# untitled.net
KiCad netlist of a schematic drawn in EAGLE
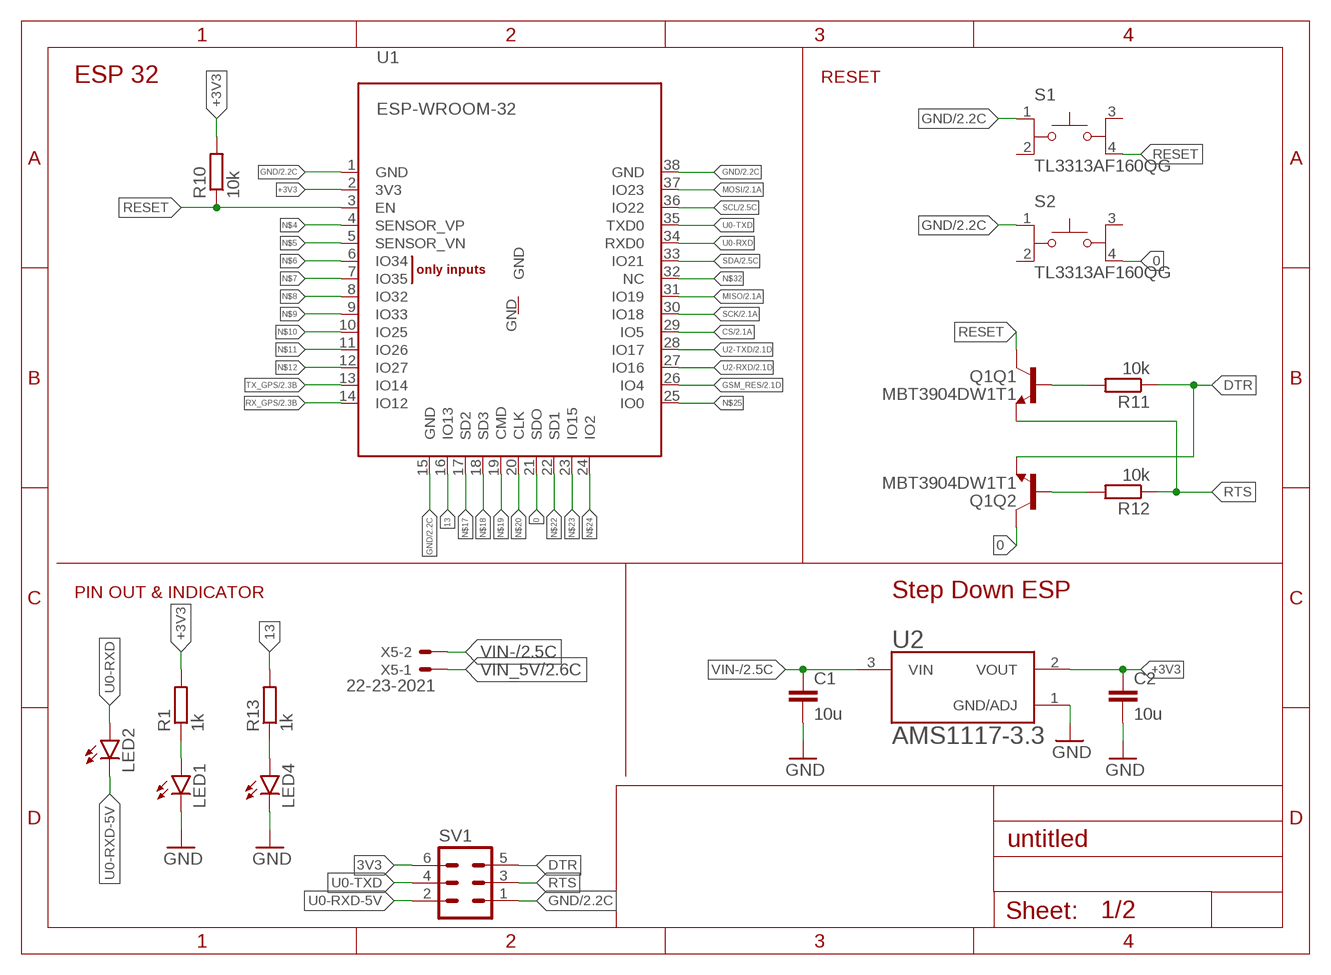
[diagram p0: schematic, sheet 1]
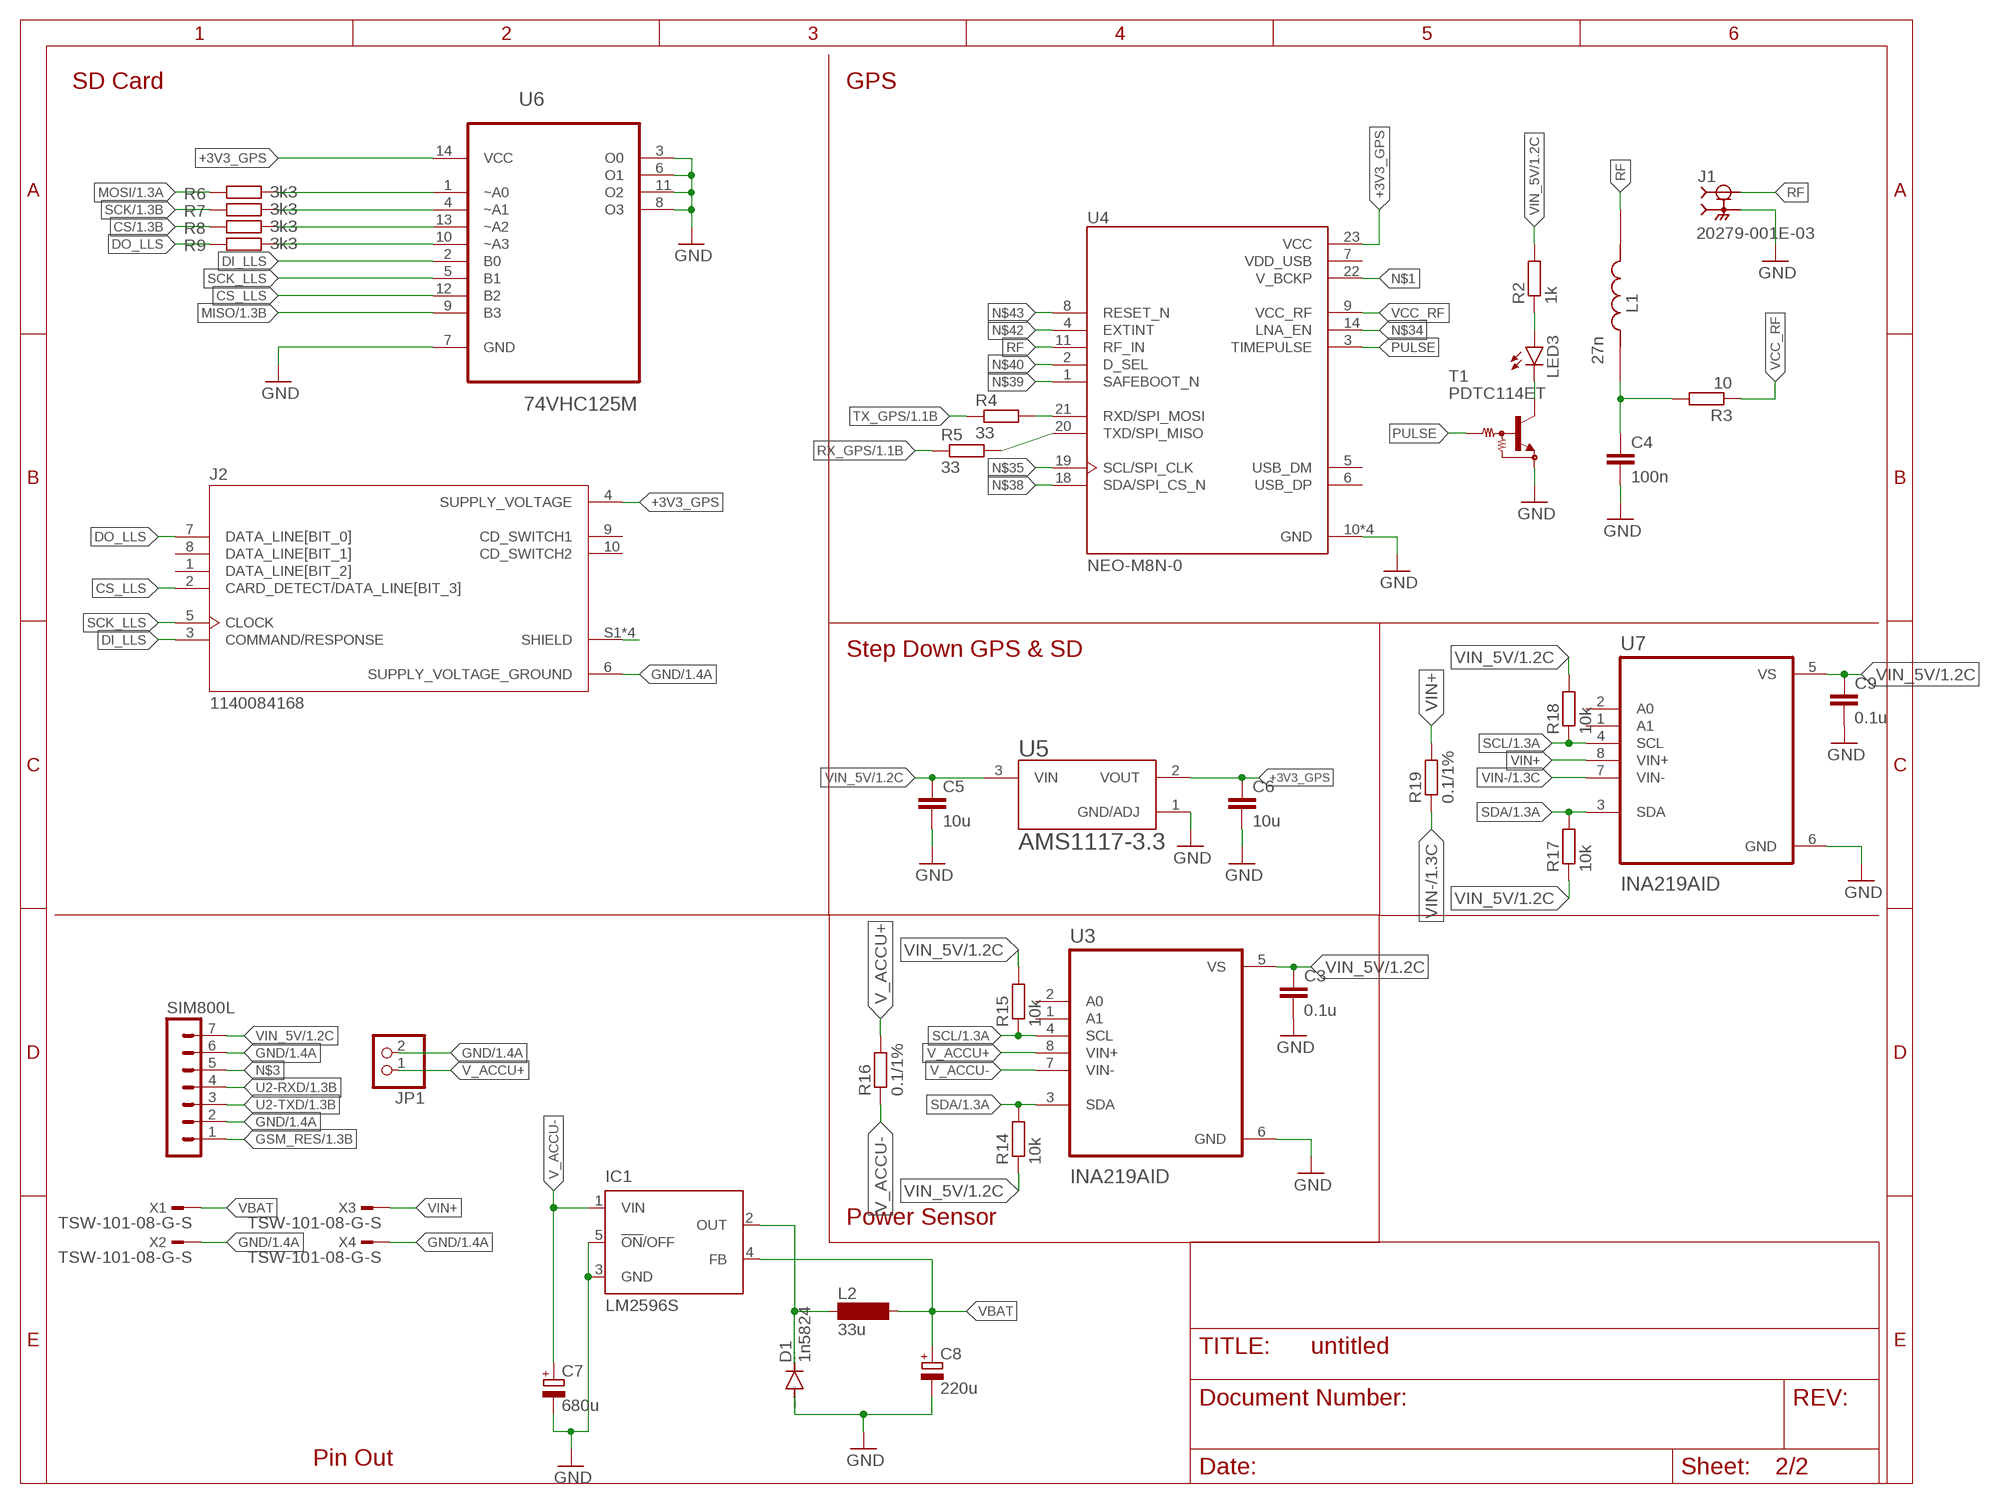
[diagram p1: schematic, sheet 2]

(export (version "E")
  (design (tool "Eeschema 10.0.6"))
  (components
    (comp (ref "C1")
      (value "10u")
      (footprint "eagle-import:C0805K")
      (libsource (lib "eagle-import") (part "C-EUC0805K"))
    )
    (comp (ref "C2")
      (value "10u")
      (footprint "eagle-import:C0805K")
      (libsource (lib "eagle-import") (part "C-EUC0805K"))
    )
    (comp (ref "LED1")
      (value "LEDCHIPLED_0805")
      (footprint "eagle-import:CHIPLED_0805")
      (libsource (lib "eagle-import") (part "LEDCHIPLED_0805"))
    )
    (comp (ref "LED2")
      (value "LEDCHIPLED_0805")
      (footprint "eagle-import:CHIPLED_0805")
      (libsource (lib "eagle-import") (part "LEDCHIPLED_0805"))
    )
    (comp (ref "LED4")
      (value "LEDCHIPLED_0805")
      (footprint "eagle-import:CHIPLED_0805")
      (libsource (lib "eagle-import") (part "LEDCHIPLED_0805"))
    )
    (comp (ref "Q1")
      (value "MBT3904DW1T1")
      (footprint "eagle-import:SC70-6")
      (fields (field (name "MF") "ON Semiconductor"))
      (libsource (lib "eagle-import") (part "MBT3904DW1T1"))
    )
    (comp (ref "R1")
      (value "1k")
      (footprint "eagle-import:M0805")
      (libsource (lib "eagle-import") (part "R-EU_M0805"))
    )
    (comp (ref "R10")
      (value "10k")
      (footprint "eagle-import:M0805")
      (libsource (lib "eagle-import") (part "R-EU_M0805"))
    )
    (comp (ref "R11")
      (value "10k")
      (footprint "eagle-import:M0805")
      (libsource (lib "eagle-import") (part "R-EU_M0805"))
    )
    (comp (ref "R12")
      (value "10k")
      (footprint "eagle-import:M0805")
      (libsource (lib "eagle-import") (part "R-EU_M0805"))
    )
    (comp (ref "R13")
      (value "1k")
      (footprint "eagle-import:M0805")
      (libsource (lib "eagle-import") (part "R-EU_M0805"))
    )
    (comp (ref "S1")
      (value "TL3313AF160QG")
      (footprint "eagle-import:SW_TL3313AF160QG")
      (fields (field (name "MF") "E-Switch"))
      (libsource (lib "eagle-import") (part "TL3313AF160QG"))
    )
    (comp (ref "S2")
      (value "TL3313AF160QG")
      (footprint "eagle-import:SW_TL3313AF160QG")
      (fields (field (name "MF") "E-Switch"))
      (libsource (lib "eagle-import") (part "TL3313AF160QG"))
    )
    (comp (ref "SV1")
      (value "MA03-2")
      (footprint "eagle-import:MA03-2")
      (libsource (lib "eagle-import") (part "MA03-2"))
    )
    (comp (ref "U1")
      (value "ESP-WROOM-32")
      (footprint "eagle-import:ESP-WROOM-32")
      (libsource (lib "eagle-import") (part "ESP-WROOM-32"))
    )
    (comp (ref "U2")
      (value "AMS1117-3.3")
      (footprint "eagle-import:SOT229P700X180-4N")
      (fields (field (name "MF") "Advanced Monolithic Systems"))
      (libsource (lib "eagle-import") (part "AMS1117-3.3"))
    )
    (comp (ref "X5")
      (value "22-23-2021")
      (footprint "eagle-import:22-23-2021")
      (fields (field (name "MF") "MOLEX"))
      (libsource (lib "eagle-import") (part "22-23-2021"))
    )
    (comp (ref "C3")
      (value "0.1u")
      (footprint "eagle-import:C0805")
      (libsource (lib "eagle-import") (part "C-EUC0805"))
    )
    (comp (ref "C4")
      (value "100n")
      (footprint "eagle-import:C0603K")
      (libsource (lib "eagle-import") (part "C-EUC0603K"))
    )
    (comp (ref "C5")
      (value "10u")
      (footprint "eagle-import:C0805K")
      (libsource (lib "eagle-import") (part "C-EUC0805K"))
    )
    (comp (ref "C6")
      (value "10u")
      (footprint "eagle-import:C0805K")
      (libsource (lib "eagle-import") (part "C-EUC0805K"))
    )
    (comp (ref "C7")
      (value "680u")
      (footprint "eagle-import:153CLV-0605")
      (libsource (lib "eagle-import") (part "CPOL-EU153CLV-0605"))
    )
    (comp (ref "C8")
      (value "220u")
      (footprint "eagle-import:153CLV-0605")
      (libsource (lib "eagle-import") (part "CPOL-EU153CLV-0605"))
    )
    (comp (ref "C9")
      (value "0.1u")
      (footprint "eagle-import:C0805")
      (libsource (lib "eagle-import") (part "C-EUC0805"))
    )
    (comp (ref "D1")
      (value "1n5824")
      (footprint "eagle-import:DO-214AC")
      (libsource (lib "eagle-import") (part "DIODE-DO-214AC"))
    )
    (comp (ref "IC1")
      (value "LM2596S")
      (footprint "eagle-import:TO263-5")
      (fields (field (name "MF") "NATIONAL SEMICONDUCTOR") (field (name "MPN") "LM2596S-ADJ/NOPB"))
      (libsource (lib "eagle-import") (part "LM2596S"))
    )
    (comp (ref "J1")
      (value "20279-001E-03")
      (footprint "eagle-import:IPEX_20279-001E-03")
      (fields (field (name "MF") "I-PEX"))
      (libsource (lib "eagle-import") (part "20279-001E-03"))
    )
    (comp (ref "J2")
      (value "1140084168")
      (footprint "eagle-import:AMPHENOL_1140084168")
      (fields (field (name "MF") "Amphenol ICC (Commercial Products)") (field (name "MP") "114-00841-68"))
      (libsource (lib "eagle-import") (part "1140084168"))
    )
    (comp (ref "JP1")
      (value "PINHD-1X2")
      (footprint "eagle-import:1X02")
      (libsource (lib "eagle-import") (part "PINHD-1X2"))
    )
    (comp (ref "L1")
      (value "27n")
      (footprint "eagle-import:INDC2012X105N")
      (fields (field (name "MF") "TDK") (field (name "MP") "MLZ2012A1R0WT000"))
      (libsource (lib "eagle-import") (part "MLZ2012A1R0WT000"))
    )
    (comp (ref "L2")
      (value "33u")
      (footprint "eagle-import:MS85")
      (libsource (lib "eagle-import") (part "MS85"))
    )
    (comp (ref "LED3")
      (value "LEDCHIPLED_0805")
      (footprint "eagle-import:CHIPLED_0805")
      (libsource (lib "eagle-import") (part "LEDCHIPLED_0805"))
    )
    (comp (ref "R2")
      (value "1k")
      (footprint "eagle-import:M0805")
      (libsource (lib "eagle-import") (part "R-EU_M0805"))
    )
    (comp (ref "R3")
      (value "10")
      (footprint "eagle-import:M1206")
      (libsource (lib "eagle-import") (part "R-EU_M1206"))
    )
    (comp (ref "R4")
      (value "33")
      (footprint "eagle-import:R1206")
      (libsource (lib "eagle-import") (part "R-EU_R1206"))
    )
    (comp (ref "R5")
      (value "33")
      (footprint "eagle-import:R1206")
      (libsource (lib "eagle-import") (part "R-EU_R1206"))
    )
    (comp (ref "R6")
      (value "3k3")
      (footprint "eagle-import:M0805")
      (libsource (lib "eagle-import") (part "R-EU_M0805"))
    )
    (comp (ref "R7")
      (value "3k3")
      (footprint "eagle-import:M0805")
      (libsource (lib "eagle-import") (part "R-EU_M0805"))
    )
    (comp (ref "R8")
      (value "3k3")
      (footprint "eagle-import:M0805")
      (libsource (lib "eagle-import") (part "R-EU_M0805"))
    )
    (comp (ref "R9")
      (value "3k3")
      (footprint "eagle-import:M0805")
      (libsource (lib "eagle-import") (part "R-EU_M0805"))
    )
    (comp (ref "R14")
      (value "10k")
      (footprint "eagle-import:M0805")
      (libsource (lib "eagle-import") (part "R-EU_M0805"))
    )
    (comp (ref "R15")
      (value "10k")
      (footprint "eagle-import:M0805")
      (libsource (lib "eagle-import") (part "R-EU_M0805"))
    )
    (comp (ref "R16")
      (value "0.1/1%")
      (footprint "eagle-import:M1206")
      (libsource (lib "eagle-import") (part "R-EU_M1206"))
    )
    (comp (ref "R17")
      (value "10k")
      (footprint "eagle-import:M0805")
      (libsource (lib "eagle-import") (part "R-EU_M0805"))
    )
    (comp (ref "R18")
      (value "10k")
      (footprint "eagle-import:M0805")
      (libsource (lib "eagle-import") (part "R-EU_M0805"))
    )
    (comp (ref "R19")
      (value "0.1/1%")
      (footprint "eagle-import:M1206")
      (libsource (lib "eagle-import") (part "R-EU_M1206"))
    )
    (comp (ref "SIM800L")
      (value "MA07-1")
      (footprint "eagle-import:MA07-1")
      (libsource (lib "eagle-import") (part "MA07-1"))
    )
    (comp (ref "T1")
      (value "PDTC114ET")
      (footprint "eagle-import:SC59-BEC")
      (libsource (lib "eagle-import") (part "-NPN_DRIVER-SC59-BECMUN2211T1"))
    )
    (comp (ref "U3")
      (value "INA219AID")
      (footprint "eagle-import:SOIC127P599X175-8N")
      (fields (field (name "MF") "Texas Instruments"))
      (libsource (lib "eagle-import") (part "INA219AID"))
    )
    (comp (ref "U4")
      (value "NEO-M8N-0")
      (footprint "eagle-import:XCVR_NEO-M8N-0")
      (fields (field (name "MF") "U-Blox America"))
      (libsource (lib "eagle-import") (part "NEO-M8N-0"))
    )
    (comp (ref "U5")
      (value "AMS1117-3.3")
      (footprint "eagle-import:SOT229P700X180-4N")
      (fields (field (name "MF") "Advanced Monolithic Systems"))
      (libsource (lib "eagle-import") (part "AMS1117-3.3"))
    )
    (comp (ref "U6")
      (value "74VHC125M")
      (footprint "eagle-import:SOIC127P600X175-14N")
      (fields (field (name "MF") "ON Semiconductor"))
      (libsource (lib "eagle-import") (part "74VHC125M"))
    )
    (comp (ref "U7")
      (value "INA219AID")
      (footprint "eagle-import:SOIC127P599X175-8N")
      (fields (field (name "MF") "Texas Instruments"))
      (libsource (lib "eagle-import") (part "INA219AID"))
    )
    (comp (ref "X1")
      (value "TSW-101-08-G-S")
      (footprint "eagle-import:TSW-101-XX-G-S")
      (fields (field (name "MF") "Samtec Inc.") (field (name "MPN") "TSW-101-07-G-S"))
      (libsource (lib "eagle-import") (part "TSW-101--G-S08"))
    )
    (comp (ref "X2")
      (value "TSW-101-08-G-S")
      (footprint "eagle-import:TSW-101-XX-G-S")
      (fields (field (name "MF") "Samtec Inc.") (field (name "MPN") "TSW-101-07-G-S"))
      (libsource (lib "eagle-import") (part "TSW-101--G-S08"))
    )
    (comp (ref "X3")
      (value "TSW-101-08-G-S")
      (footprint "eagle-import:TSW-101-XX-G-S")
      (fields (field (name "MF") "Samtec Inc.") (field (name "MPN") "TSW-101-07-G-S"))
      (libsource (lib "eagle-import") (part "TSW-101--G-S08"))
    )
    (comp (ref "X4")
      (value "TSW-101-08-G-S")
      (footprint "eagle-import:TSW-101-XX-G-S")
      (fields (field (name "MF") "Samtec Inc.") (field (name "MPN") "TSW-101-07-G-S"))
      (libsource (lib "eagle-import") (part "TSW-101--G-S08"))
    )
  )
  (nets
    (net (code "1") (name "+3V3") (class "Default")
      (node (ref "C2") (pin "1") (pinfunction "1_1") (pintype "passive"))
      (node (ref "R1") (pin "2") (pinfunction "2_2") (pintype "passive"))
      (node (ref "R10") (pin "2") (pinfunction "2_2") (pintype "passive"))
      (node (ref "U1") (pin "2") (pinfunction "3V3_2") (pintype "bidirectional"))
      (node (ref "U2") (pin "2") (pinfunction "VOUT_2") (pintype "output"))
    )
    (net (code "2") (name "+3V3_GPS") (class "Default")
      (node (ref "C6") (pin "1") (pinfunction "1_1") (pintype "passive"))
      (node (ref "J2") (pin "4") (pinfunction "SUPPLY_VOLTAGE_4") (pintype "power_in"))
      (node (ref "U4") (pin "23") (pinfunction "VCC_23") (pintype "power_in"))
      (node (ref "U5") (pin "2") (pinfunction "VOUT_2") (pintype "output"))
      (node (ref "U6") (pin "14") (pinfunction "VCC_14") (pintype "power_in"))
    )
    (net (code "3") (name "0") (class "Default")
      (node (ref "Q1") (pin "6") (pinfunction "C_6") (pintype "passive"))
      (node (ref "S2") (pin "4") (pinfunction "4_4") (pintype "passive"))
      (node (ref "U1") (pin "21") (pinfunction "SDO_21") (pintype "bidirectional"))
    )
    (net (code "4") (name "3V3") (class "Default")
      (node (ref "SV1") (pin "6") (pinfunction "6_6") (pintype "passive"))
    )
    (net (code "5") (name "13") (class "Default")
      (node (ref "R13") (pin "2") (pinfunction "2_2") (pintype "passive"))
      (node (ref "U1") (pin "16") (pinfunction "IO13_16") (pintype "bidirectional"))
    )
    (net (code "6") (name "CS") (class "Default")
      (node (ref "R8") (pin "1") (pinfunction "1_1") (pintype "passive"))
      (node (ref "U1") (pin "29") (pinfunction "IO5_29") (pintype "bidirectional"))
    )
    (net (code "7") (name "CS_LLS") (class "Default")
      (node (ref "J2") (pin "2") (pinfunction "CARD_DETECT/DATA_LINE[BIT_3]_2") (pintype "bidirectional"))
      (node (ref "U6") (pin "12") (pinfunction "B2_12") (pintype "input"))
    )
    (net (code "8") (name "DI_LLS") (class "Default")
      (node (ref "J2") (pin "3") (pinfunction "COMMAND/RESPONSE_3") (pintype "bidirectional"))
      (node (ref "U6") (pin "2") (pinfunction "B0_2") (pintype "input"))
    )
    (net (code "9") (name "DO_LLS") (class "Default")
      (node (ref "J2") (pin "7") (pinfunction "DATA_LINE[BIT_0]_7") (pintype "bidirectional"))
      (node (ref "R9") (pin "1") (pinfunction "1_1") (pintype "passive"))
    )
    (net (code "10") (name "DTR") (class "Default")
      (node (ref "Q1") (pin "1") (pinfunction "E_1") (pintype "passive"))
      (node (ref "R11") (pin "1") (pinfunction "1_1") (pintype "passive"))
      (node (ref "SV1") (pin "5") (pinfunction "5_5") (pintype "passive"))
    )
    (net (code "11") (name "GND") (class "Default")
      (node (ref "C1") (pin "2") (pinfunction "2_2") (pintype "passive"))
      (node (ref "C2") (pin "2") (pinfunction "2_2") (pintype "passive"))
      (node (ref "C3") (pin "2") (pinfunction "2_2") (pintype "passive"))
      (node (ref "C4") (pin "2") (pinfunction "2_2") (pintype "passive"))
      (node (ref "C5") (pin "2") (pinfunction "2_2") (pintype "passive"))
      (node (ref "C6") (pin "2") (pinfunction "2_2") (pintype "passive"))
      (node (ref "C7") (pin "-") (pinfunction "-_-") (pintype "passive"))
      (node (ref "C8") (pin "-") (pinfunction "-_-") (pintype "passive"))
      (node (ref "C9") (pin "2") (pinfunction "2_2") (pintype "passive"))
      (node (ref "D1") (pin "A") (pinfunction "A_A") (pintype "passive"))
      (node (ref "IC1") (pin "3") (pinfunction "GND_3") (pintype "power_in"))
      (node (ref "IC1") (pin "5") (pinfunction "~{ON}/OFF_5") (pintype "input"))
      (node (ref "J1") (pin "2") (pinfunction "GND_2") (pintype "passive"))
      (node (ref "J1") (pin "3") (pinfunction "GND_3") (pintype "passive"))
      (node (ref "J2") (pin "6") (pinfunction "SUPPLY_VOLTAGE_GROUND_6") (pintype "power_in"))
      (node (ref "JP1") (pin "2") (pinfunction "2_2") (pintype "passive"))
      (node (ref "LED1") (pin "C") (pinfunction "C_C") (pintype "passive"))
      (node (ref "LED4") (pin "C") (pinfunction "C_C") (pintype "passive"))
      (node (ref "S1") (pin "1") (pinfunction "1_1") (pintype "passive"))
      (node (ref "S2") (pin "1") (pinfunction "1_1") (pintype "passive"))
      (node (ref "SIM800L") (pin "2") (pinfunction "2_2") (pintype "passive"))
      (node (ref "SIM800L") (pin "6") (pinfunction "6_6") (pintype "passive"))
      (node (ref "SV1") (pin "1") (pinfunction "1_1") (pintype "passive"))
      (node (ref "T1") (pin "E") (pinfunction "E_E") (pintype "passive"))
      (node (ref "U1") (pin "1") (pinfunction "GND_1") (pintype "bidirectional"))
      (node (ref "U1") (pin "15") (pinfunction "GND_15") (pintype "bidirectional"))
      (node (ref "U1") (pin "38") (pinfunction "GND_38") (pintype "bidirectional"))
      (node (ref "U2") (pin "1") (pinfunction "GND/ADJ_1") (pintype "power_in"))
      (node (ref "U3") (pin "6") (pinfunction "GND_6") (pintype "power_in"))
      (node (ref "U4") (pin "10") (pinfunction "GND_10") (pintype "power_in"))
      (node (ref "U4") (pin "12") (pinfunction "GND_12") (pintype "power_in"))
      (node (ref "U4") (pin "13") (pinfunction "GND_13") (pintype "power_in"))
      (node (ref "U4") (pin "24") (pinfunction "GND_24") (pintype "power_in"))
      (node (ref "U5") (pin "1") (pinfunction "GND/ADJ_1") (pintype "power_in"))
      (node (ref "U6") (pin "11") (pinfunction "O2_11") (pintype "output"))
      (node (ref "U6") (pin "3") (pinfunction "O0_3") (pintype "output"))
      (node (ref "U6") (pin "6") (pinfunction "O1_6") (pintype "output"))
      (node (ref "U6") (pin "7") (pinfunction "GND_7") (pintype "passive"))
      (node (ref "U6") (pin "8") (pinfunction "O3_8") (pintype "output"))
      (node (ref "U7") (pin "6") (pinfunction "GND_6") (pintype "power_in"))
      (node (ref "X2") (pin "1") (pinfunction "1_1") (pintype "passive"))
      (node (ref "X4") (pin "1") (pinfunction "1_1") (pintype "passive"))
    )
    (net (code "12") (name "GSM_RES") (class "Default")
      (node (ref "SIM800L") (pin "1") (pinfunction "1_1") (pintype "passive"))
      (node (ref "U1") (pin "26") (pinfunction "IO4_26") (pintype "bidirectional"))
    )
    (net (code "13") (name "MISO") (class "Default")
      (node (ref "U1") (pin "31") (pinfunction "IO19_31") (pintype "bidirectional"))
      (node (ref "U6") (pin "9") (pinfunction "B3_9") (pintype "input"))
    )
    (net (code "14") (name "MOSI") (class "Default")
      (node (ref "R6") (pin "1") (pinfunction "1_1") (pintype "passive"))
      (node (ref "U1") (pin "37") (pinfunction "IO23_37") (pintype "bidirectional"))
    )
    (net (code "15") (name "N$1") (class "Default")
      (node (ref "U4") (pin "22") (pinfunction "V_BCKP_22") (pintype "power_in"))
    )
    (net (code "16") (name "N$3") (class "Default")
      (node (ref "SIM800L") (pin "5") (pinfunction "5_5") (pintype "passive"))
    )
    (net (code "17") (name "N$4") (class "Default")
      (node (ref "U1") (pin "4") (pinfunction "SENSOR_VP_4") (pintype "input"))
    )
    (net (code "18") (name "N$5") (class "Default")
      (node (ref "U1") (pin "5") (pinfunction "SENSOR_VN_5") (pintype "input"))
    )
    (net (code "19") (name "N$6") (class "Default")
      (node (ref "U1") (pin "6") (pinfunction "IO34_6") (pintype "input"))
    )
    (net (code "20") (name "N$7") (class "Default")
      (node (ref "U1") (pin "7") (pinfunction "IO35_7") (pintype "input"))
    )
    (net (code "21") (name "N$8") (class "Default")
      (node (ref "U1") (pin "8") (pinfunction "IO32_8") (pintype "bidirectional"))
    )
    (net (code "22") (name "N$9") (class "Default")
      (node (ref "U1") (pin "9") (pinfunction "IO33_9") (pintype "bidirectional"))
    )
    (net (code "23") (name "N$10") (class "Default")
      (node (ref "U1") (pin "10") (pinfunction "IO25_10") (pintype "bidirectional"))
    )
    (net (code "24") (name "N$11") (class "Default")
      (node (ref "U1") (pin "11") (pinfunction "IO26_11") (pintype "bidirectional"))
    )
    (net (code "25") (name "N$12") (class "Default")
      (node (ref "U1") (pin "12") (pinfunction "IO27_12") (pintype "bidirectional"))
    )
    (net (code "26") (name "N$17") (class "Default")
      (node (ref "U1") (pin "17") (pinfunction "SD2_17") (pintype "bidirectional"))
    )
    (net (code "27") (name "N$18") (class "Default")
      (node (ref "U1") (pin "18") (pinfunction "SD3_18") (pintype "bidirectional"))
    )
    (net (code "28") (name "N$19") (class "Default")
      (node (ref "U1") (pin "19") (pinfunction "CMD_19") (pintype "bidirectional"))
    )
    (net (code "29") (name "N$20") (class "Default")
      (node (ref "U1") (pin "20") (pinfunction "CLK_20") (pintype "bidirectional"))
    )
    (net (code "30") (name "N$22") (class "Default")
      (node (ref "U1") (pin "22") (pinfunction "SD1_22") (pintype "bidirectional"))
    )
    (net (code "31") (name "N$23") (class "Default")
      (node (ref "U1") (pin "23") (pinfunction "IO15_23") (pintype "bidirectional"))
    )
    (net (code "32") (name "N$24") (class "Default")
      (node (ref "U1") (pin "24") (pinfunction "IO2_24") (pintype "bidirectional"))
    )
    (net (code "33") (name "N$25") (class "Default")
      (node (ref "U1") (pin "25") (pinfunction "IO0_25") (pintype "bidirectional"))
    )
    (net (code "34") (name "N$32") (class "Default")
      (node (ref "U1") (pin "32") (pinfunction "NC_32") (pintype "bidirectional"))
    )
    (net (code "35") (name "N$34") (class "Default")
      (node (ref "U4") (pin "14") (pinfunction "LNA_EN_14") (pintype "output"))
    )
    (net (code "36") (name "N$35") (class "Default")
      (node (ref "U4") (pin "19") (pinfunction "SCL/SPI_CLK_19") (pintype "input"))
    )
    (net (code "37") (name "N$38") (class "Default")
      (node (ref "U4") (pin "18") (pinfunction "SDA/SPI_CS_N_18") (pintype "bidirectional"))
    )
    (net (code "38") (name "N$39") (class "Default")
      (node (ref "U4") (pin "1") (pinfunction "SAFEBOOT_N_1") (pintype "input"))
    )
    (net (code "39") (name "N$40") (class "Default")
      (node (ref "U4") (pin "2") (pinfunction "D_SEL_2") (pintype "input"))
    )
    (net (code "40") (name "N$42") (class "Default")
      (node (ref "U4") (pin "4") (pinfunction "EXTINT_4") (pintype "input"))
    )
    (net (code "41") (name "N$43") (class "Default")
      (node (ref "U4") (pin "8") (pinfunction "RESET_N_8") (pintype "input"))
    )
    (net (code "42") (name "Net-(C4-Pad1)") (class "Default")
      (node (ref "C4") (pin "1") (pinfunction "1_1") (pintype "passive"))
      (node (ref "L1") (pin "1") (pinfunction "1_1") (pintype "passive"))
      (node (ref "R3") (pin "2") (pinfunction "2_2") (pintype "passive"))
    )
    (net (code "43") (name "Net-(IC1-OUT)") (class "Default")
      (node (ref "D1") (pin "C") (pinfunction "C_C") (pintype "passive"))
      (node (ref "IC1") (pin "2") (pinfunction "OUT_2") (pintype "output"))
      (node (ref "L2") (pin "1") (pinfunction "1_1") (pintype "passive"))
    )
    (net (code "44") (name "Net-(J2-SHIELD-PadS1)") (class "Default")
      (node (ref "J2") (pin "S1") (pinfunction "SHIELD_S1") (pintype "passive"))
      (node (ref "J2") (pin "S2") (pinfunction "SHIELD_S2") (pintype "passive"))
      (node (ref "J2") (pin "S3") (pinfunction "SHIELD_S3") (pintype "passive"))
      (node (ref "J2") (pin "S4") (pinfunction "SHIELD_S4") (pintype "passive"))
    )
    (net (code "45") (name "Net-(LED1-PadA)") (class "Default")
      (node (ref "LED1") (pin "A") (pinfunction "A_A") (pintype "passive"))
      (node (ref "R1") (pin "1") (pinfunction "1_1") (pintype "passive"))
    )
    (net (code "46") (name "Net-(LED3-PadA)") (class "Default")
      (node (ref "LED3") (pin "A") (pinfunction "A_A") (pintype "passive"))
      (node (ref "R2") (pin "1") (pinfunction "1_1") (pintype "passive"))
    )
    (net (code "47") (name "Net-(LED3-PadC)") (class "Default")
      (node (ref "LED3") (pin "C") (pinfunction "C_C") (pintype "passive"))
      (node (ref "T1") (pin "C") (pinfunction "C_C") (pintype "passive"))
    )
    (net (code "48") (name "Net-(LED4-PadA)") (class "Default")
      (node (ref "LED4") (pin "A") (pinfunction "A_A") (pintype "passive"))
      (node (ref "R13") (pin "1") (pinfunction "1_1") (pintype "passive"))
    )
    (net (code "49") (name "Net-(Q1A-B)") (class "Default")
      (node (ref "Q1") (pin "5") (pinfunction "B_5") (pintype "passive"))
      (node (ref "R11") (pin "2") (pinfunction "2_2") (pintype "passive"))
    )
    (net (code "50") (name "Net-(Q1B-B)") (class "Default")
      (node (ref "Q1") (pin "2") (pinfunction "B_2") (pintype "passive"))
      (node (ref "R12") (pin "2") (pinfunction "2_2") (pintype "passive"))
    )
    (net (code "51") (name "Net-(U4-RXD{slash}SPI_MOSI)") (class "Default")
      (node (ref "R4") (pin "2") (pinfunction "2_2") (pintype "passive"))
      (node (ref "U4") (pin "21") (pinfunction "RXD/SPI_MOSI_21") (pintype "input"))
    )
    (net (code "52") (name "Net-(U4-TXD{slash}SPI_MISO)") (class "Default")
      (node (ref "R5") (pin "2") (pinfunction "2_2") (pintype "passive"))
      (node (ref "U4") (pin "20") (pinfunction "TXD/SPI_MISO_20") (pintype "output"))
    )
    (net (code "53") (name "Net-(U6-~{A0})") (class "Default")
      (node (ref "R6") (pin "2") (pinfunction "2_2") (pintype "passive"))
      (node (ref "U6") (pin "1") (pinfunction "~{A0}_1") (pintype "input"))
    )
    (net (code "54") (name "Net-(U6-~{A1})") (class "Default")
      (node (ref "R7") (pin "2") (pinfunction "2_2") (pintype "passive"))
      (node (ref "U6") (pin "4") (pinfunction "~{A1}_4") (pintype "input"))
    )
    (net (code "55") (name "Net-(U6-~{A2})") (class "Default")
      (node (ref "R8") (pin "2") (pinfunction "2_2") (pintype "passive"))
      (node (ref "U6") (pin "13") (pinfunction "~{A2}_13") (pintype "input"))
    )
    (net (code "56") (name "Net-(U6-~{A3})") (class "Default")
      (node (ref "R9") (pin "2") (pinfunction "2_2") (pintype "passive"))
      (node (ref "U6") (pin "10") (pinfunction "~{A3}_10") (pintype "input"))
    )
    (net (code "57") (name "PULSE") (class "Default")
      (node (ref "T1") (pin "B") (pinfunction "B_B") (pintype "passive"))
      (node (ref "U4") (pin "3") (pinfunction "TIMEPULSE_3") (pintype "output"))
    )
    (net (code "58") (name "RESET") (class "Default")
      (node (ref "Q1") (pin "3") (pinfunction "C_3") (pintype "passive"))
      (node (ref "R10") (pin "1") (pinfunction "1_1") (pintype "passive"))
      (node (ref "S1") (pin "4") (pinfunction "4_4") (pintype "passive"))
      (node (ref "U1") (pin "3") (pinfunction "EN_3") (pintype "bidirectional"))
    )
    (net (code "59") (name "RF") (class "Default")
      (node (ref "J1") (pin "1") (pinfunction "SIG_1") (pintype "passive"))
      (node (ref "L1") (pin "2") (pinfunction "2_2") (pintype "passive"))
      (node (ref "U4") (pin "11") (pinfunction "RF_IN_11") (pintype "input"))
    )
    (net (code "60") (name "RTS") (class "Default")
      (node (ref "Q1") (pin "4") (pinfunction "E_4") (pintype "passive"))
      (node (ref "R12") (pin "1") (pinfunction "1_1") (pintype "passive"))
      (node (ref "SV1") (pin "3") (pinfunction "3_3") (pintype "passive"))
    )
    (net (code "61") (name "RX_GPS") (class "Default")
      (node (ref "R5") (pin "1") (pinfunction "1_1") (pintype "passive"))
      (node (ref "U1") (pin "14") (pinfunction "IO12_14") (pintype "bidirectional"))
    )
    (net (code "62") (name "SCK") (class "Default")
      (node (ref "R7") (pin "1") (pinfunction "1_1") (pintype "passive"))
      (node (ref "U1") (pin "30") (pinfunction "IO18_30") (pintype "bidirectional"))
    )
    (net (code "63") (name "SCK_LLS") (class "Default")
      (node (ref "J2") (pin "5") (pinfunction "CLOCK_5") (pintype "bidirectional"))
      (node (ref "U6") (pin "5") (pinfunction "B1_5") (pintype "input"))
    )
    (net (code "64") (name "SCL") (class "Default")
      (node (ref "R15") (pin "1") (pinfunction "1_1") (pintype "passive"))
      (node (ref "R18") (pin "1") (pinfunction "1_1") (pintype "passive"))
      (node (ref "U1") (pin "36") (pinfunction "IO22_36") (pintype "bidirectional"))
      (node (ref "U3") (pin "4") (pinfunction "SCL_4") (pintype "input"))
      (node (ref "U7") (pin "4") (pinfunction "SCL_4") (pintype "input"))
    )
    (net (code "65") (name "SDA") (class "Default")
      (node (ref "R14") (pin "2") (pinfunction "2_2") (pintype "passive"))
      (node (ref "R17") (pin "2") (pinfunction "2_2") (pintype "passive"))
      (node (ref "U1") (pin "33") (pinfunction "IO21_33") (pintype "bidirectional"))
      (node (ref "U3") (pin "3") (pinfunction "SDA_3") (pintype "bidirectional"))
      (node (ref "U7") (pin "3") (pinfunction "SDA_3") (pintype "bidirectional"))
    )
    (net (code "66") (name "TX_GPS") (class "Default")
      (node (ref "R4") (pin "1") (pinfunction "1_1") (pintype "passive"))
      (node (ref "U1") (pin "13") (pinfunction "IO14_13") (pintype "bidirectional"))
    )
    (net (code "67") (name "U0-RXD") (class "Default")
      (node (ref "LED2") (pin "A") (pinfunction "A_A") (pintype "passive"))
      (node (ref "U1") (pin "34") (pinfunction "RXD0_34") (pintype "bidirectional"))
    )
    (net (code "68") (name "U0-RXD-5V") (class "Default")
      (node (ref "LED2") (pin "C") (pinfunction "C_C") (pintype "passive"))
      (node (ref "SV1") (pin "2") (pinfunction "2_2") (pintype "passive"))
    )
    (net (code "69") (name "U0-TXD") (class "Default")
      (node (ref "SV1") (pin "4") (pinfunction "4_4") (pintype "passive"))
      (node (ref "U1") (pin "35") (pinfunction "TXD0_35") (pintype "bidirectional"))
    )
    (net (code "70") (name "U2-RXD") (class "Default")
      (node (ref "SIM800L") (pin "4") (pinfunction "4_4") (pintype "passive"))
      (node (ref "U1") (pin "27") (pinfunction "IO16_27") (pintype "bidirectional"))
    )
    (net (code "71") (name "U2-TXD") (class "Default")
      (node (ref "SIM800L") (pin "3") (pinfunction "3_3") (pintype "passive"))
      (node (ref "U1") (pin "28") (pinfunction "IO17_28") (pintype "bidirectional"))
    )
    (net (code "72") (name "VBAT") (class "Default")
      (node (ref "C8") (pin "+") (pinfunction "+_+") (pintype "passive"))
      (node (ref "IC1") (pin "4") (pinfunction "FB_4") (pintype "input"))
      (node (ref "L2") (pin "2") (pinfunction "2_2") (pintype "passive"))
      (node (ref "X1") (pin "1") (pinfunction "1_1") (pintype "passive"))
    )
    (net (code "73") (name "VCC_RF") (class "Default")
      (node (ref "R3") (pin "1") (pinfunction "1_1") (pintype "passive"))
      (node (ref "U4") (pin "9") (pinfunction "VCC_RF_9") (pintype "output"))
    )
    (net (code "74") (name "VDD_USB") (class "Default")
      (node (ref "U4") (pin "7") (pinfunction "VDD_USB_7") (pintype "power_in"))
    )
    (net (code "75") (name "VIN+") (class "Default")
      (node (ref "R19") (pin "2") (pinfunction "2_2") (pintype "passive"))
      (node (ref "U7") (pin "8") (pinfunction "VIN+_8") (pintype "input"))
      (node (ref "X3") (pin "1") (pinfunction "1_1") (pintype "passive"))
    )
    (net (code "76") (name "VIN-") (class "Default")
      (node (ref "C1") (pin "1") (pinfunction "1_1") (pintype "passive"))
      (node (ref "R19") (pin "1") (pinfunction "1_1") (pintype "passive"))
      (node (ref "U2") (pin "3") (pinfunction "VIN_3") (pintype "input"))
      (node (ref "U7") (pin "7") (pinfunction "VIN-_7") (pintype "input"))
      (node (ref "X5") (pin "2") (pinfunction "S_2") (pintype "passive"))
    )
    (net (code "77") (name "VIN_5V") (class "Default")
      (node (ref "C3") (pin "1") (pinfunction "1_1") (pintype "passive"))
      (node (ref "C5") (pin "1") (pinfunction "1_1") (pintype "passive"))
      (node (ref "C9") (pin "1") (pinfunction "1_1") (pintype "passive"))
      (node (ref "R14") (pin "1") (pinfunction "1_1") (pintype "passive"))
      (node (ref "R15") (pin "2") (pinfunction "2_2") (pintype "passive"))
      (node (ref "R17") (pin "1") (pinfunction "1_1") (pintype "passive"))
      (node (ref "R18") (pin "2") (pinfunction "2_2") (pintype "passive"))
      (node (ref "R2") (pin "2") (pinfunction "2_2") (pintype "passive"))
      (node (ref "SIM800L") (pin "7") (pinfunction "7_7") (pintype "passive"))
      (node (ref "U3") (pin "5") (pinfunction "VS_5") (pintype "power_in"))
      (node (ref "U5") (pin "3") (pinfunction "VIN_3") (pintype "input"))
      (node (ref "U7") (pin "5") (pinfunction "VS_5") (pintype "power_in"))
      (node (ref "X5") (pin "1") (pinfunction "S_1") (pintype "passive"))
    )
    (net (code "78") (name "V_ACCU+") (class "Default")
      (node (ref "JP1") (pin "1") (pinfunction "1_1") (pintype "passive"))
      (node (ref "R16") (pin "2") (pinfunction "2_2") (pintype "passive"))
      (node (ref "U3") (pin "8") (pinfunction "VIN+_8") (pintype "input"))
    )
    (net (code "79") (name "V_ACCU-") (class "Default")
      (node (ref "C7") (pin "+") (pinfunction "+_+") (pintype "passive"))
      (node (ref "IC1") (pin "1") (pinfunction "VIN_1") (pintype "input"))
      (node (ref "R16") (pin "1") (pinfunction "1_1") (pintype "passive"))
      (node (ref "U3") (pin "7") (pinfunction "VIN-_7") (pintype "input"))
    )
    (net (code "80") (name "unconnected-(J2-CD_SWITCH1-Pad9)") (class "Default")
      (node (ref "J2") (pin "9") (pinfunction "CD_SWITCH1_9") (pintype "bidirectional"))
    )
    (net (code "81") (name "unconnected-(J2-CD_SWITCH2-Pad10)") (class "Default")
      (node (ref "J2") (pin "10") (pinfunction "CD_SWITCH2_10") (pintype "bidirectional"))
    )
    (net (code "82") (name "unconnected-(J2-DATA_LINE[BIT_1]-Pad8)") (class "Default")
      (node (ref "J2") (pin "8") (pinfunction "DATA_LINE[BIT_1]_8") (pintype "bidirectional"))
    )
    (net (code "83") (name "unconnected-(J2-DATA_LINE[BIT_2]-Pad1)") (class "Default")
      (node (ref "J2") (pin "1") (pinfunction "DATA_LINE[BIT_2]_1") (pintype "bidirectional"))
    )
    (net (code "84") (name "unconnected-(S1-Pad2)") (class "Default")
      (node (ref "S1") (pin "2") (pinfunction "2_2") (pintype "passive"))
    )
    (net (code "85") (name "unconnected-(S1-Pad3)") (class "Default")
      (node (ref "S1") (pin "3") (pinfunction "3_3") (pintype "passive"))
    )
    (net (code "86") (name "unconnected-(S2-Pad2)") (class "Default")
      (node (ref "S2") (pin "2") (pinfunction "2_2") (pintype "passive"))
    )
    (net (code "87") (name "unconnected-(S2-Pad3)") (class "Default")
      (node (ref "S2") (pin "3") (pinfunction "3_3") (pintype "passive"))
    )
    (net (code "88") (name "unconnected-(U1-PadGND)") (class "Default")
      (node (ref "U1") (pin "GND") (pinfunction "GND_GND") (pintype "bidirectional"))
    )
    (net (code "89") (name "unconnected-(U3-A0-Pad2)") (class "Default")
      (node (ref "U3") (pin "2") (pinfunction "A0_2") (pintype "input"))
    )
    (net (code "90") (name "unconnected-(U3-A1-Pad1)") (class "Default")
      (node (ref "U3") (pin "1") (pinfunction "A1_1") (pintype "input"))
    )
    (net (code "91") (name "unconnected-(U4-USB_DM-Pad5)") (class "Default")
      (node (ref "U4") (pin "5") (pinfunction "USB_DM_5") (pintype "bidirectional"))
    )
    (net (code "92") (name "unconnected-(U4-USB_DP-Pad6)") (class "Default")
      (node (ref "U4") (pin "6") (pinfunction "USB_DP_6") (pintype "bidirectional"))
    )
    (net (code "93") (name "unconnected-(U7-A0-Pad2)") (class "Default")
      (node (ref "U7") (pin "2") (pinfunction "A0_2") (pintype "input"))
    )
    (net (code "94") (name "unconnected-(U7-A1-Pad1)") (class "Default")
      (node (ref "U7") (pin "1") (pinfunction "A1_1") (pintype "input"))
    )
  )
)
